# ARCAdaptor.net
KiCad netlist of a schematic drawn in EAGLE
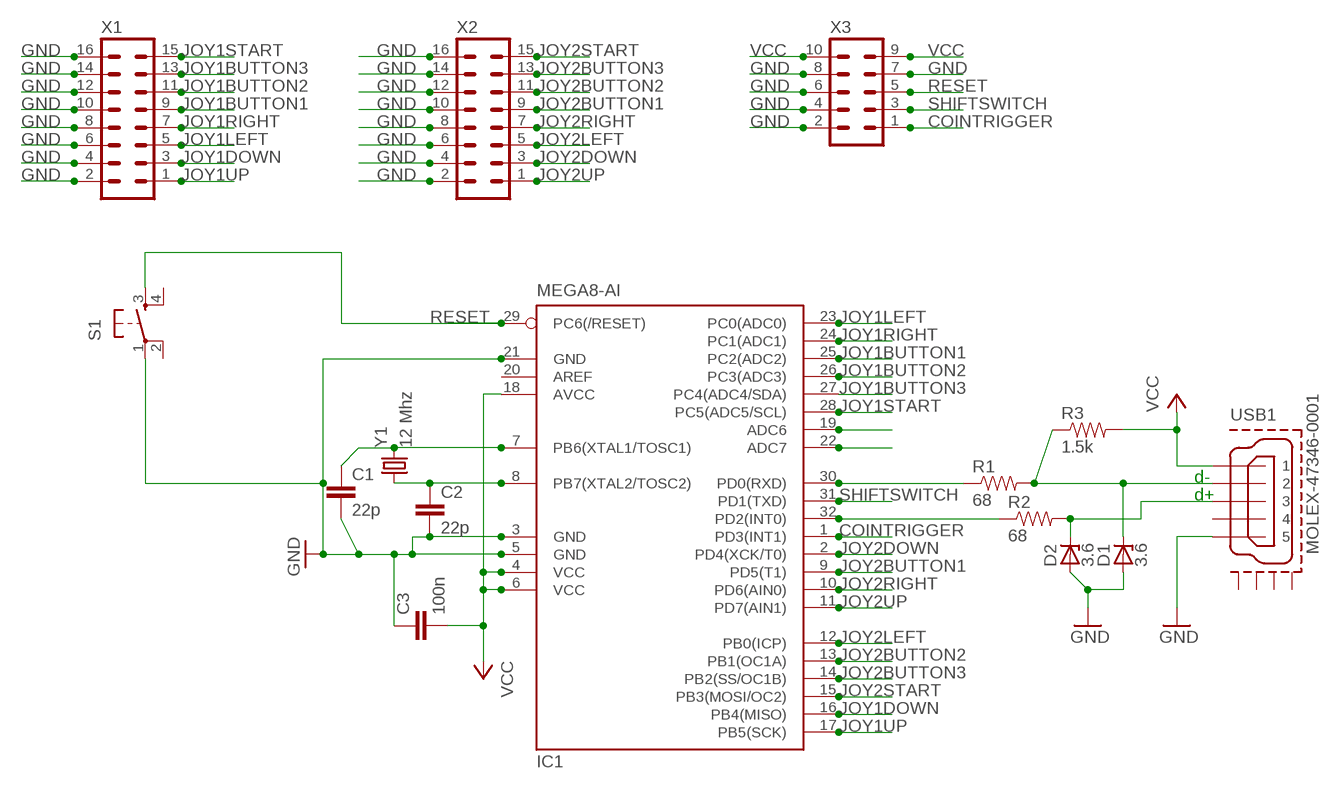
[diagram p0: schematic, sheet 1]

(export (version "E")
  (design (tool "Eeschema 10.0.6"))
  (components
    (comp (ref "C1")
      (value "22p")
      (footprint "eagle-import:0805")
      (libsource (lib "eagle-import") (part "CAP0805"))
    )
    (comp (ref "C2")
      (value "22p")
      (footprint "eagle-import:0805")
      (libsource (lib "eagle-import") (part "CAP0805"))
    )
    (comp (ref "C3")
      (value "100n")
      (footprint "eagle-import:0805")
      (libsource (lib "eagle-import") (part "CAP0805"))
    )
    (comp (ref "D1")
      (value "3.6")
      (footprint "eagle-import:SOT23")
      (libsource (lib "eagle-import") (part "ZENER-DIODESOT23"))
    )
    (comp (ref "D2")
      (value "3.6")
      (footprint "eagle-import:SOT23")
      (libsource (lib "eagle-import") (part "ZENER-DIODESOT23"))
    )
    (comp (ref "IC1")
      (value "MEGA8-AI")
      (footprint "eagle-import:TQFP32-08")
      (fields (field (name "MPN") "ATMEGA8-16AU"))
      (libsource (lib "eagle-import") (part "MEGA8-AI"))
    )
    (comp (ref "R1")
      (value "68")
      (footprint "eagle-import:0805")
      (libsource (lib "eagle-import") (part "RESISTOR0805-RES"))
    )
    (comp (ref "R2")
      (value "68")
      (footprint "eagle-import:0805")
      (libsource (lib "eagle-import") (part "RESISTOR0805-RES"))
    )
    (comp (ref "R3")
      (value "1.5k")
      (footprint "eagle-import:0805")
      (libsource (lib "eagle-import") (part "RESISTOR0805-RES"))
    )
    (comp (ref "S1")
      (value "TAC_SWITCHSMD")
      (footprint "eagle-import:TACTILE_SWITCH_SMD")
      (libsource (lib "eagle-import") (part "TAC_SWITCHSMD"))
    )
    (comp (ref "USB1")
      (value "MOLEX-47346-0001")
      (footprint "eagle-import:MOLEX-47364-0001")
      (libsource (lib "eagle-import") (part "MOLEX-47346-0001"))
    )
    (comp (ref "X1")
      (value "MA08-2")
      (footprint "eagle-import:MA08-2")
      (libsource (lib "eagle-import") (part "MA08-2"))
    )
    (comp (ref "X2")
      (value "MA08-2")
      (footprint "eagle-import:MA08-2")
      (libsource (lib "eagle-import") (part "MA08-2"))
    )
    (comp (ref "X3")
      (value "MA05-2")
      (footprint "eagle-import:MA05-2")
      (libsource (lib "eagle-import") (part "MA05-2"))
    )
    (comp (ref "Y1")
      (value "12 Mhz")
      (footprint "eagle-import:CRYSTAL-SMD-5X3")
      (libsource (lib "eagle-import") (part "CRYSTAL5X3"))
    )
  )
  (nets
    (net (code "1") (name "/COINTRIGGER") (class "Default")
      (node (ref "IC1") (pin "1") (pinfunction "PD3(INT1)_1") (pintype "bidirectional"))
      (node (ref "X3") (pin "1") (pinfunction "1_1") (pintype "passive"))
    )
    (net (code "2") (name "/JOY1BUTTON1") (class "Default")
      (node (ref "IC1") (pin "25") (pinfunction "PC2(ADC2)_25") (pintype "bidirectional"))
      (node (ref "X1") (pin "9") (pinfunction "9_9") (pintype "passive"))
    )
    (net (code "3") (name "/JOY1BUTTON2") (class "Default")
      (node (ref "IC1") (pin "26") (pinfunction "PC3(ADC3)_26") (pintype "bidirectional"))
      (node (ref "X1") (pin "11") (pinfunction "11_11") (pintype "passive"))
    )
    (net (code "4") (name "/JOY1BUTTON3") (class "Default")
      (node (ref "IC1") (pin "27") (pinfunction "PC4(ADC4/SDA)_27") (pintype "bidirectional"))
      (node (ref "X1") (pin "13") (pinfunction "13_13") (pintype "passive"))
    )
    (net (code "5") (name "/JOY1DOWN") (class "Default")
      (node (ref "IC1") (pin "16") (pinfunction "PB4(MISO)_16") (pintype "bidirectional"))
      (node (ref "X1") (pin "3") (pinfunction "3_3") (pintype "passive"))
    )
    (net (code "6") (name "/JOY1LEFT") (class "Default")
      (node (ref "IC1") (pin "23") (pinfunction "PC0(ADC0)_23") (pintype "bidirectional"))
      (node (ref "X1") (pin "5") (pinfunction "5_5") (pintype "passive"))
    )
    (net (code "7") (name "/JOY1RIGHT") (class "Default")
      (node (ref "IC1") (pin "24") (pinfunction "PC1(ADC1)_24") (pintype "bidirectional"))
      (node (ref "X1") (pin "7") (pinfunction "7_7") (pintype "passive"))
    )
    (net (code "8") (name "/JOY1START") (class "Default")
      (node (ref "IC1") (pin "28") (pinfunction "PC5(ADC5/SCL)_28") (pintype "bidirectional"))
      (node (ref "X1") (pin "15") (pinfunction "15_15") (pintype "passive"))
    )
    (net (code "9") (name "/JOY1UP") (class "Default")
      (node (ref "IC1") (pin "17") (pinfunction "PB5(SCK)_17") (pintype "bidirectional"))
      (node (ref "X1") (pin "1") (pinfunction "1_1") (pintype "passive"))
    )
    (net (code "10") (name "/JOY2BUTTON1") (class "Default")
      (node (ref "IC1") (pin "9") (pinfunction "PD5(T1)_9") (pintype "bidirectional"))
      (node (ref "X2") (pin "9") (pinfunction "9_9") (pintype "passive"))
    )
    (net (code "11") (name "/JOY2BUTTON2") (class "Default")
      (node (ref "IC1") (pin "13") (pinfunction "PB1(OC1A)_13") (pintype "bidirectional"))
      (node (ref "X2") (pin "11") (pinfunction "11_11") (pintype "passive"))
    )
    (net (code "12") (name "/JOY2BUTTON3") (class "Default")
      (node (ref "IC1") (pin "14") (pinfunction "PB2(SS/OC1B)_14") (pintype "bidirectional"))
      (node (ref "X2") (pin "13") (pinfunction "13_13") (pintype "passive"))
    )
    (net (code "13") (name "/JOY2DOWN") (class "Default")
      (node (ref "IC1") (pin "2") (pinfunction "PD4(XCK/T0)_2") (pintype "bidirectional"))
      (node (ref "X2") (pin "3") (pinfunction "3_3") (pintype "passive"))
    )
    (net (code "14") (name "/JOY2LEFT") (class "Default")
      (node (ref "IC1") (pin "12") (pinfunction "PB0(ICP)_12") (pintype "bidirectional"))
      (node (ref "X2") (pin "5") (pinfunction "5_5") (pintype "passive"))
    )
    (net (code "15") (name "/JOY2RIGHT") (class "Default")
      (node (ref "IC1") (pin "10") (pinfunction "PD6(AIN0)_10") (pintype "bidirectional"))
      (node (ref "X2") (pin "7") (pinfunction "7_7") (pintype "passive"))
    )
    (net (code "16") (name "/JOY2START") (class "Default")
      (node (ref "IC1") (pin "15") (pinfunction "PB3(MOSI/OC2)_15") (pintype "bidirectional"))
      (node (ref "X2") (pin "15") (pinfunction "15_15") (pintype "passive"))
    )
    (net (code "17") (name "/JOY2UP") (class "Default")
      (node (ref "IC1") (pin "11") (pinfunction "PD7(AIN1)_11") (pintype "bidirectional"))
      (node (ref "X2") (pin "1") (pinfunction "1_1") (pintype "passive"))
    )
    (net (code "18") (name "/RESET") (class "Default")
      (node (ref "IC1") (pin "29") (pinfunction "PC6(/RESET)_29") (pintype "bidirectional"))
      (node (ref "S1") (pin "3") (pinfunction "3_3") (pintype "passive"))
      (node (ref "X3") (pin "5") (pinfunction "5_5") (pintype "passive"))
    )
    (net (code "19") (name "/SHIFTSWITCH") (class "Default")
      (node (ref "IC1") (pin "31") (pinfunction "PD1(TXD)_31") (pintype "bidirectional"))
      (node (ref "X3") (pin "3") (pinfunction "3_3") (pintype "passive"))
    )
    (net (code "20") (name "GND") (class "Default")
      (node (ref "C1") (pin "2") (pinfunction "2_2") (pintype "passive"))
      (node (ref "C2") (pin "2") (pinfunction "2_2") (pintype "passive"))
      (node (ref "C3") (pin "1") (pinfunction "1_1") (pintype "passive"))
      (node (ref "D1") (pin "1") (pinfunction "A_1") (pintype "passive"))
      (node (ref "D2") (pin "1") (pinfunction "A_1") (pintype "passive"))
      (node (ref "IC1") (pin "21") (pinfunction "GND_21") (pintype "power_in"))
      (node (ref "IC1") (pin "3") (pinfunction "GND_3") (pintype "power_in"))
      (node (ref "IC1") (pin "5") (pinfunction "GND_5") (pintype "power_in"))
      (node (ref "S1") (pin "1") (pinfunction "1_1") (pintype "passive"))
      (node (ref "USB1") (pin "5") (pinfunction "5_5") (pintype "input"))
      (node (ref "X1") (pin "10") (pinfunction "10_10") (pintype "passive"))
      (node (ref "X1") (pin "12") (pinfunction "12_12") (pintype "passive"))
      (node (ref "X1") (pin "14") (pinfunction "14_14") (pintype "passive"))
      (node (ref "X1") (pin "16") (pinfunction "16_16") (pintype "passive"))
      (node (ref "X1") (pin "2") (pinfunction "2_2") (pintype "passive"))
      (node (ref "X1") (pin "4") (pinfunction "4_4") (pintype "passive"))
      (node (ref "X1") (pin "6") (pinfunction "6_6") (pintype "passive"))
      (node (ref "X1") (pin "8") (pinfunction "8_8") (pintype "passive"))
      (node (ref "X2") (pin "10") (pinfunction "10_10") (pintype "passive"))
      (node (ref "X2") (pin "12") (pinfunction "12_12") (pintype "passive"))
      (node (ref "X2") (pin "14") (pinfunction "14_14") (pintype "passive"))
      (node (ref "X2") (pin "16") (pinfunction "16_16") (pintype "passive"))
      (node (ref "X2") (pin "2") (pinfunction "2_2") (pintype "passive"))
      (node (ref "X2") (pin "4") (pinfunction "4_4") (pintype "passive"))
      (node (ref "X2") (pin "6") (pinfunction "6_6") (pintype "passive"))
      (node (ref "X2") (pin "8") (pinfunction "8_8") (pintype "passive"))
      (node (ref "X3") (pin "2") (pinfunction "2_2") (pintype "passive"))
      (node (ref "X3") (pin "4") (pinfunction "4_4") (pintype "passive"))
      (node (ref "X3") (pin "6") (pinfunction "6_6") (pintype "passive"))
      (node (ref "X3") (pin "7") (pinfunction "7_7") (pintype "passive"))
      (node (ref "X3") (pin "8") (pinfunction "8_8") (pintype "passive"))
    )
    (net (code "21") (name "Net-(D1-C)") (class "Default")
      (node (ref "D1") (pin "3") (pinfunction "C_3") (pintype "passive"))
      (node (ref "R1") (pin "2") (pinfunction "2_2") (pintype "passive"))
      (node (ref "R3") (pin "1") (pinfunction "1_1") (pintype "passive"))
      (node (ref "USB1") (pin "2") (pinfunction "2_2") (pintype "input"))
    )
    (net (code "22") (name "Net-(D2-C)") (class "Default")
      (node (ref "D2") (pin "3") (pinfunction "C_3") (pintype "passive"))
      (node (ref "R2") (pin "2") (pinfunction "2_2") (pintype "passive"))
      (node (ref "USB1") (pin "3") (pinfunction "3_3") (pintype "input"))
    )
    (net (code "23") (name "Net-(IC1-PB6(XTAL1{slash}TOSC1))") (class "Default")
      (node (ref "C1") (pin "1") (pinfunction "1_1") (pintype "passive"))
      (node (ref "IC1") (pin "7") (pinfunction "PB6(XTAL1/TOSC1)_7") (pintype "bidirectional"))
      (node (ref "Y1") (pin "3") (pinfunction "2_3") (pintype "passive"))
    )
    (net (code "24") (name "Net-(IC1-PB7(XTAL2{slash}TOSC2))") (class "Default")
      (node (ref "C2") (pin "1") (pinfunction "1_1") (pintype "passive"))
      (node (ref "IC1") (pin "8") (pinfunction "PB7(XTAL2/TOSC2)_8") (pintype "bidirectional"))
      (node (ref "Y1") (pin "1") (pinfunction "1_1") (pintype "passive"))
    )
    (net (code "25") (name "Net-(IC1-PD0(RXD))") (class "Default")
      (node (ref "IC1") (pin "30") (pinfunction "PD0(RXD)_30") (pintype "bidirectional"))
      (node (ref "R1") (pin "1") (pinfunction "1_1") (pintype "passive"))
    )
    (net (code "26") (name "Net-(IC1-PD2(INT0))") (class "Default")
      (node (ref "IC1") (pin "32") (pinfunction "PD2(INT0)_32") (pintype "bidirectional"))
      (node (ref "R2") (pin "1") (pinfunction "1_1") (pintype "passive"))
    )
    (net (code "27") (name "VCC") (class "Default")
      (node (ref "C3") (pin "2") (pinfunction "2_2") (pintype "passive"))
      (node (ref "IC1") (pin "18") (pinfunction "AVCC_18") (pintype "power_in"))
      (node (ref "IC1") (pin "4") (pinfunction "VCC_4") (pintype "power_in"))
      (node (ref "IC1") (pin "6") (pinfunction "VCC_6") (pintype "power_in"))
      (node (ref "R3") (pin "2") (pinfunction "2_2") (pintype "passive"))
      (node (ref "USB1") (pin "1") (pinfunction "1_1") (pintype "input"))
      (node (ref "X3") (pin "10") (pinfunction "10_10") (pintype "passive"))
      (node (ref "X3") (pin "9") (pinfunction "9_9") (pintype "passive"))
    )
    (net (code "28") (name "unconnected-(IC1-ADC6-Pad19)") (class "Default")
      (node (ref "IC1") (pin "19") (pinfunction "ADC6_19") (pintype "bidirectional"))
    )
    (net (code "29") (name "unconnected-(IC1-ADC7-Pad22)") (class "Default")
      (node (ref "IC1") (pin "22") (pinfunction "ADC7_22") (pintype "bidirectional"))
    )
    (net (code "30") (name "unconnected-(IC1-AREF-Pad20)") (class "Default")
      (node (ref "IC1") (pin "20") (pinfunction "AREF_20") (pintype "passive"))
    )
    (net (code "31") (name "unconnected-(S1-Pad2)") (class "Default")
      (node (ref "S1") (pin "2") (pinfunction "2_2") (pintype "passive"))
    )
    (net (code "32") (name "unconnected-(S1-Pad4)") (class "Default")
      (node (ref "S1") (pin "4") (pinfunction "4_4") (pintype "passive"))
    )
    (net (code "33") (name "unconnected-(USB1-Pad4)") (class "Default")
      (node (ref "USB1") (pin "4") (pinfunction "4_4") (pintype "input"))
    )
    (net (code "34") (name "unconnected-(USB1-PadGND1)") (class "Default")
      (node (ref "USB1") (pin "GND1") (pinfunction "GND1_GND1") (pintype "bidirectional"))
    )
    (net (code "35") (name "unconnected-(USB1-PadGND2)") (class "Default")
      (node (ref "USB1") (pin "GND2") (pinfunction "GND2_GND2") (pintype "bidirectional"))
    )
    (net (code "36") (name "unconnected-(USB1-PadGND3)") (class "Default")
      (node (ref "USB1") (pin "GND3") (pinfunction "GND3_GND3") (pintype "bidirectional"))
    )
    (net (code "37") (name "unconnected-(USB1-PadGND4)") (class "Default")
      (node (ref "USB1") (pin "GND4") (pinfunction "GND4_GND4") (pintype "bidirectional"))
    )
  )
)
